# Accelerometer.net
KiCad netlist of a schematic drawn in Altium Designer
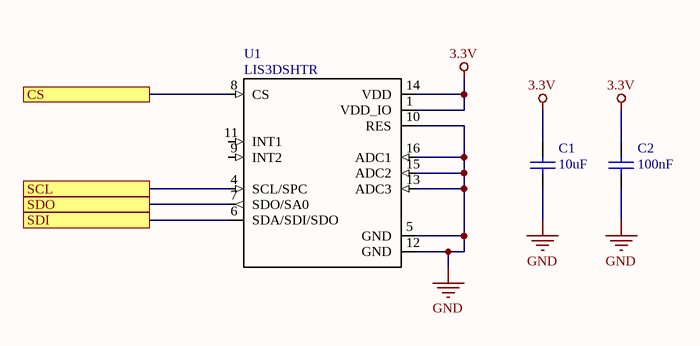
[diagram p0: Accelerometer.SchDoc]

(export (version "E")
  (design (tool "Eeschema 10.0.6"))
  (components
    (comp (ref "C1")
      (value "10uF")
      (footprint "0603 to 1210 SMD")
      (fields (field (name "Comment") "Cap"))
      (libsource (lib "RC0805FR-0751K1L") (part "Cap"))
    )
    (comp (ref "C2")
      (value "100nF")
      (footprint "0603 to 0805 SMD")
      (fields (field (name "Comment") "Cap"))
      (libsource (lib "RC0805FR-0751K1L") (part "Cap"))
    )
    (comp (ref "U1")
      (value "LIS3DSHTR")
      (footprint "L3GD20HTR")
      (fields (field (name "MF") "STMicroelectronics"))
      (libsource (lib "AvionicsParts") (part "LIS3DSHTR"))
    )
  )
  (nets
    (net (code "1") (name "/CS") (class "Default")
      (node (ref "U1") (pin "8") (pinfunction "CS_8") (pintype "input"))
    )
    (net (code "2") (name "/SCL") (class "Default")
      (node (ref "U1") (pin "4") (pinfunction "SCL/SPC_4") (pintype "input"))
    )
    (net (code "3") (name "/SDI") (class "Default")
      (node (ref "U1") (pin "6") (pinfunction "SDA/SDI/SDO_6") (pintype "bidirectional"))
    )
    (net (code "4") (name "/SDO") (class "Default")
      (node (ref "U1") (pin "7") (pinfunction "SDO/SA0_7") (pintype "output"))
    )
    (net (code "5") (name "3.3V") (class "Default")
      (node (ref "C1") (pin "2") (pinfunction "2_2") (pintype "passive"))
      (node (ref "C2") (pin "2") (pinfunction "2_2") (pintype "passive"))
      (node (ref "U1") (pin "1") (pinfunction "VDD_IO_1") (pintype "power_in"))
      (node (ref "U1") (pin "14") (pinfunction "VDD_14") (pintype "power_in"))
    )
    (net (code "6") (name "GND") (class "Default")
      (node (ref "C1") (pin "1") (pinfunction "1_1") (pintype "passive"))
      (node (ref "C2") (pin "1") (pinfunction "1_1") (pintype "passive"))
      (node (ref "U1") (pin "10") (pinfunction "RES_10") (pintype "power_in"))
      (node (ref "U1") (pin "12") (pinfunction "GND_12") (pintype "power_in"))
      (node (ref "U1") (pin "13") (pinfunction "ADC3_13") (pintype "input"))
      (node (ref "U1") (pin "15") (pinfunction "ADC2_15") (pintype "input"))
      (node (ref "U1") (pin "16") (pinfunction "ADC1_16") (pintype "input"))
      (node (ref "U1") (pin "5") (pinfunction "GND_5") (pintype "power_in"))
    )
    (net (code "7") (name "unconnected-(U1-INT1-Pad11)") (class "Default")
      (node (ref "U1") (pin "11") (pinfunction "INT1_11") (pintype "input"))
    )
    (net (code "8") (name "unconnected-(U1-INT2-Pad9)") (class "Default")
      (node (ref "U1") (pin "9") (pinfunction "INT2_9") (pintype "input"))
    )
  )
)
